# BTB_CONN.net
KiCad netlist of a schematic drawn in Altium Designer
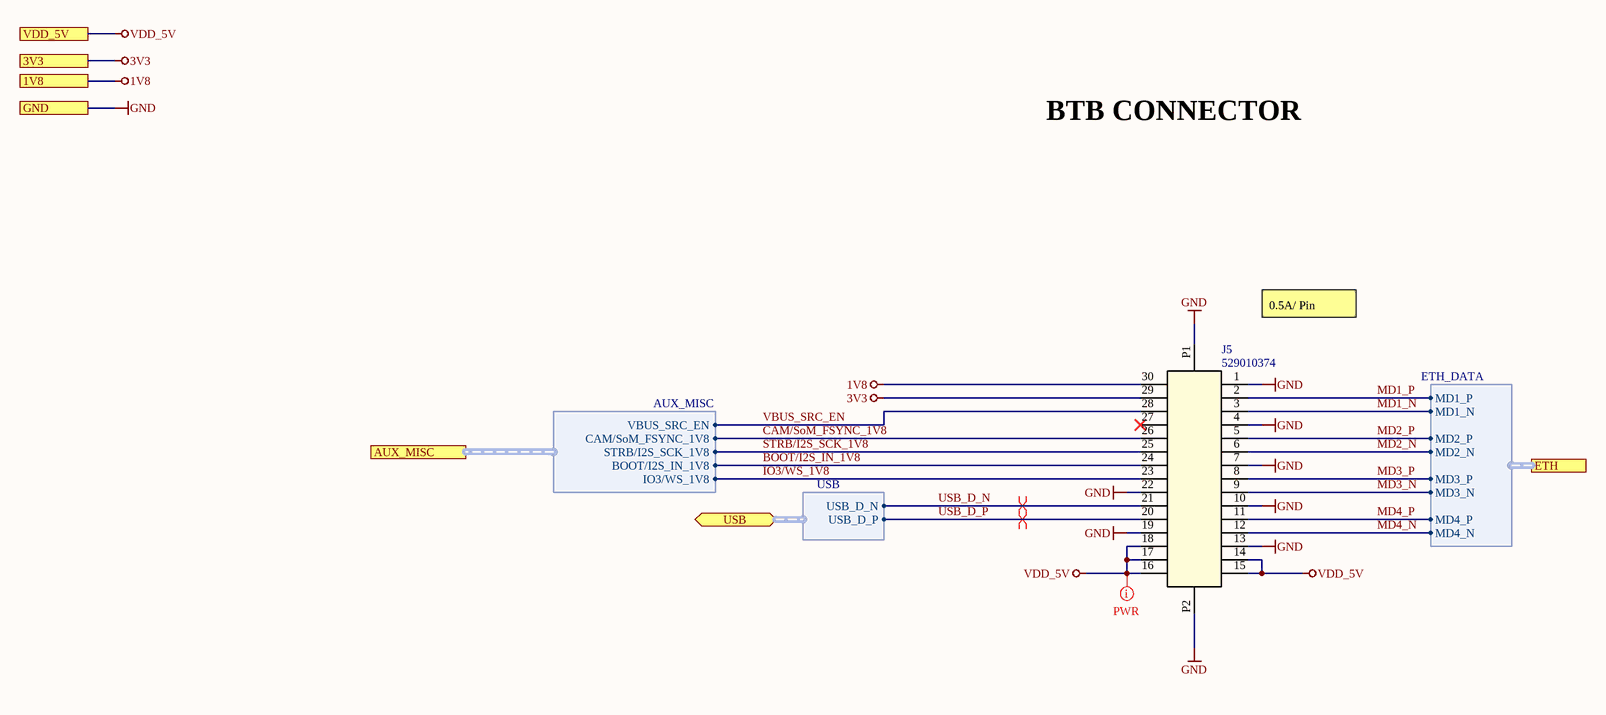
[diagram p0: BTB_CONN.SchDoc]

(export (version "E")
  (design (tool "Eeschema 10.0.6"))
  (components
    (comp (ref "J5")
      (value "529010374")
      (footprint "CON_529010374")
      (libsource (lib "Luxonis LLC") (part "529010374"))
    )
  )
  (nets
    (net (code "4") (name "/BOOT{slash}I2S_IN_1V8") (class "Default")
      (node (ref "J5") (pin "24") (pinfunction "24_24") (pintype "passive"))
    )
    (net (code "5") (name "/CAM{slash}SoM_FSYNC_1V8") (class "Default")
      (node (ref "J5") (pin "26") (pinfunction "26_26") (pintype "passive"))
    )
    (net (code "6") (name "/IO3{slash}WS_1V8") (class "Default")
      (node (ref "J5") (pin "23") (pinfunction "23_23") (pintype "passive"))
    )
    (net (code "7") (name "/MD1_N") (class "Default")
      (node (ref "J5") (pin "3") (pinfunction "3_3") (pintype "passive"))
    )
    (net (code "8") (name "/MD1_P") (class "Default")
      (node (ref "J5") (pin "2") (pinfunction "2_2") (pintype "passive"))
    )
    (net (code "9") (name "/MD2_N") (class "Default")
      (node (ref "J5") (pin "6") (pinfunction "6_6") (pintype "passive"))
    )
    (net (code "10") (name "/MD2_P") (class "Default")
      (node (ref "J5") (pin "5") (pinfunction "5_5") (pintype "passive"))
    )
    (net (code "11") (name "/MD3_N") (class "Default")
      (node (ref "J5") (pin "9") (pinfunction "9_9") (pintype "passive"))
    )
    (net (code "12") (name "/MD3_P") (class "Default")
      (node (ref "J5") (pin "8") (pinfunction "8_8") (pintype "passive"))
    )
    (net (code "13") (name "/MD4_N") (class "Default")
      (node (ref "J5") (pin "12") (pinfunction "12_12") (pintype "passive"))
    )
    (net (code "14") (name "/MD4_P") (class "Default")
      (node (ref "J5") (pin "11") (pinfunction "11_11") (pintype "passive"))
    )
    (net (code "15") (name "/STRB{slash}I2S_SCK_1V8") (class "Default")
      (node (ref "J5") (pin "25") (pinfunction "25_25") (pintype "passive"))
    )
    (net (code "16") (name "/USB_D_N") (class "Default")
      (node (ref "J5") (pin "21") (pinfunction "21_21") (pintype "passive"))
    )
    (net (code "17") (name "/USB_D_P") (class "Default")
      (node (ref "J5") (pin "20") (pinfunction "20_20") (pintype "passive"))
    )
    (net (code "18") (name "/VBUS_SRC_EN") (class "Default")
      (node (ref "J5") (pin "28") (pinfunction "28_28") (pintype "passive"))
    )
    (net (code "22") (name "1V8") (class "Default")
      (node (ref "J5") (pin "30") (pinfunction "30_30") (pintype "passive"))
    )
    (net (code "23") (name "3V3") (class "Default")
      (node (ref "J5") (pin "29") (pinfunction "29_29") (pintype "passive"))
    )
    (net (code "24") (name "GND") (class "Default")
      (node (ref "J5") (pin "1") (pinfunction "1_1") (pintype "passive"))
      (node (ref "J5") (pin "10") (pinfunction "10_10") (pintype "passive"))
      (node (ref "J5") (pin "13") (pinfunction "13_13") (pintype "passive"))
      (node (ref "J5") (pin "19") (pinfunction "19_19") (pintype "passive"))
      (node (ref "J5") (pin "22") (pinfunction "22_22") (pintype "passive"))
      (node (ref "J5") (pin "4") (pinfunction "4_4") (pintype "passive"))
      (node (ref "J5") (pin "7") (pinfunction "7_7") (pintype "passive"))
      (node (ref "J5") (pin "P1") (pinfunction "P1_P1") (pintype "passive"))
      (node (ref "J5") (pin "P2") (pinfunction "P2_P2") (pintype "passive"))
    )
    (net (code "25") (name "VDD_5V") (class "Default")
      (node (ref "J5") (pin "14") (pinfunction "14_14") (pintype "passive"))
      (node (ref "J5") (pin "15") (pinfunction "15_15") (pintype "passive"))
      (node (ref "J5") (pin "16") (pinfunction "16_16") (pintype "passive"))
      (node (ref "J5") (pin "17") (pinfunction "17_17") (pintype "passive"))
      (node (ref "J5") (pin "18") (pinfunction "18_18") (pintype "passive"))
    )
    (net (code "26") (name "unconnected-(J5-Pad27)") (class "Default")
      (node (ref "J5") (pin "27") (pinfunction "27_27") (pintype "passive+no_connect"))
    )
  )
)
